# main.net
KiCad netlist of a schematic drawn in Altium Designer
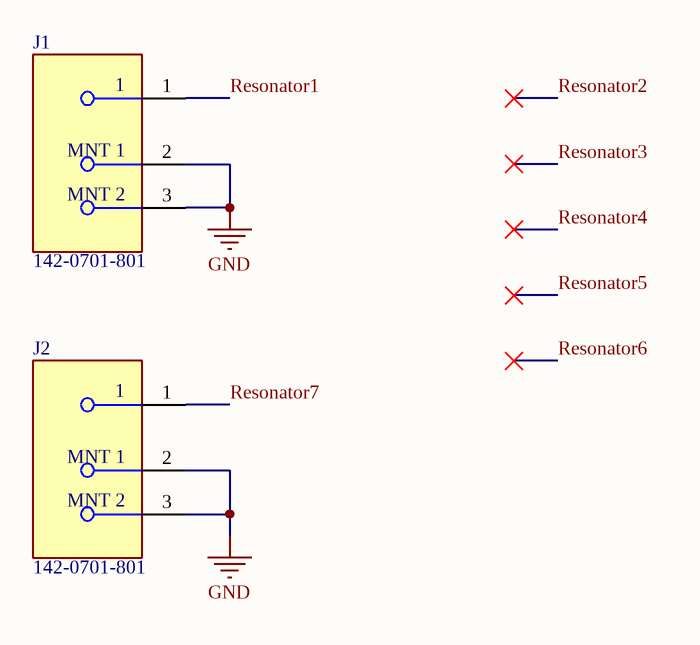
[diagram p0: main.SchDoc]

(export (version "E")
  (design (tool "Eeschema 10.0.6"))
  (components
    (comp (ref "J1")
      (value "142-0701-801")
      (footprint "FP-142-0701-801-MFG")
      (description "CONN SMA JACK STR 50OHM EDGE MNT")
      (libsource (lib "Altium Content Vault") (part "89929399afe843c8b6880c6cbd0f99a"))
    )
    (comp (ref "J2")
      (value "142-0701-801")
      (footprint "FP-142-0701-801-MFG")
      (description "CONN SMA JACK STR 50OHM EDGE MNT")
      (libsource (lib "Altium Content Vault") (part "89929399afe843c8b6880c6cbd0f99a"))
    )
  )
  (nets
    (net (code "1") (name "/Resonator1") (class "Default")
      (node (ref "J1") (pin "1") (pinfunction "1_1") (pintype "passive"))
    )
    (net (code "7") (name "/Resonator7") (class "Default")
      (node (ref "J2") (pin "1") (pinfunction "1_1") (pintype "passive"))
    )
    (net (code "8") (name "GND") (class "Default")
      (node (ref "J1") (pin "2") (pinfunction "MNT_1_2") (pintype "passive"))
      (node (ref "J1") (pin "3") (pinfunction "MNT_2_3") (pintype "passive"))
      (node (ref "J2") (pin "2") (pinfunction "MNT_1_2") (pintype "passive"))
      (node (ref "J2") (pin "3") (pinfunction "MNT_2_3") (pintype "passive"))
    )
  )
)
